# gigafoc.net
KiCad netlist of a schematic drawn in EAGLE
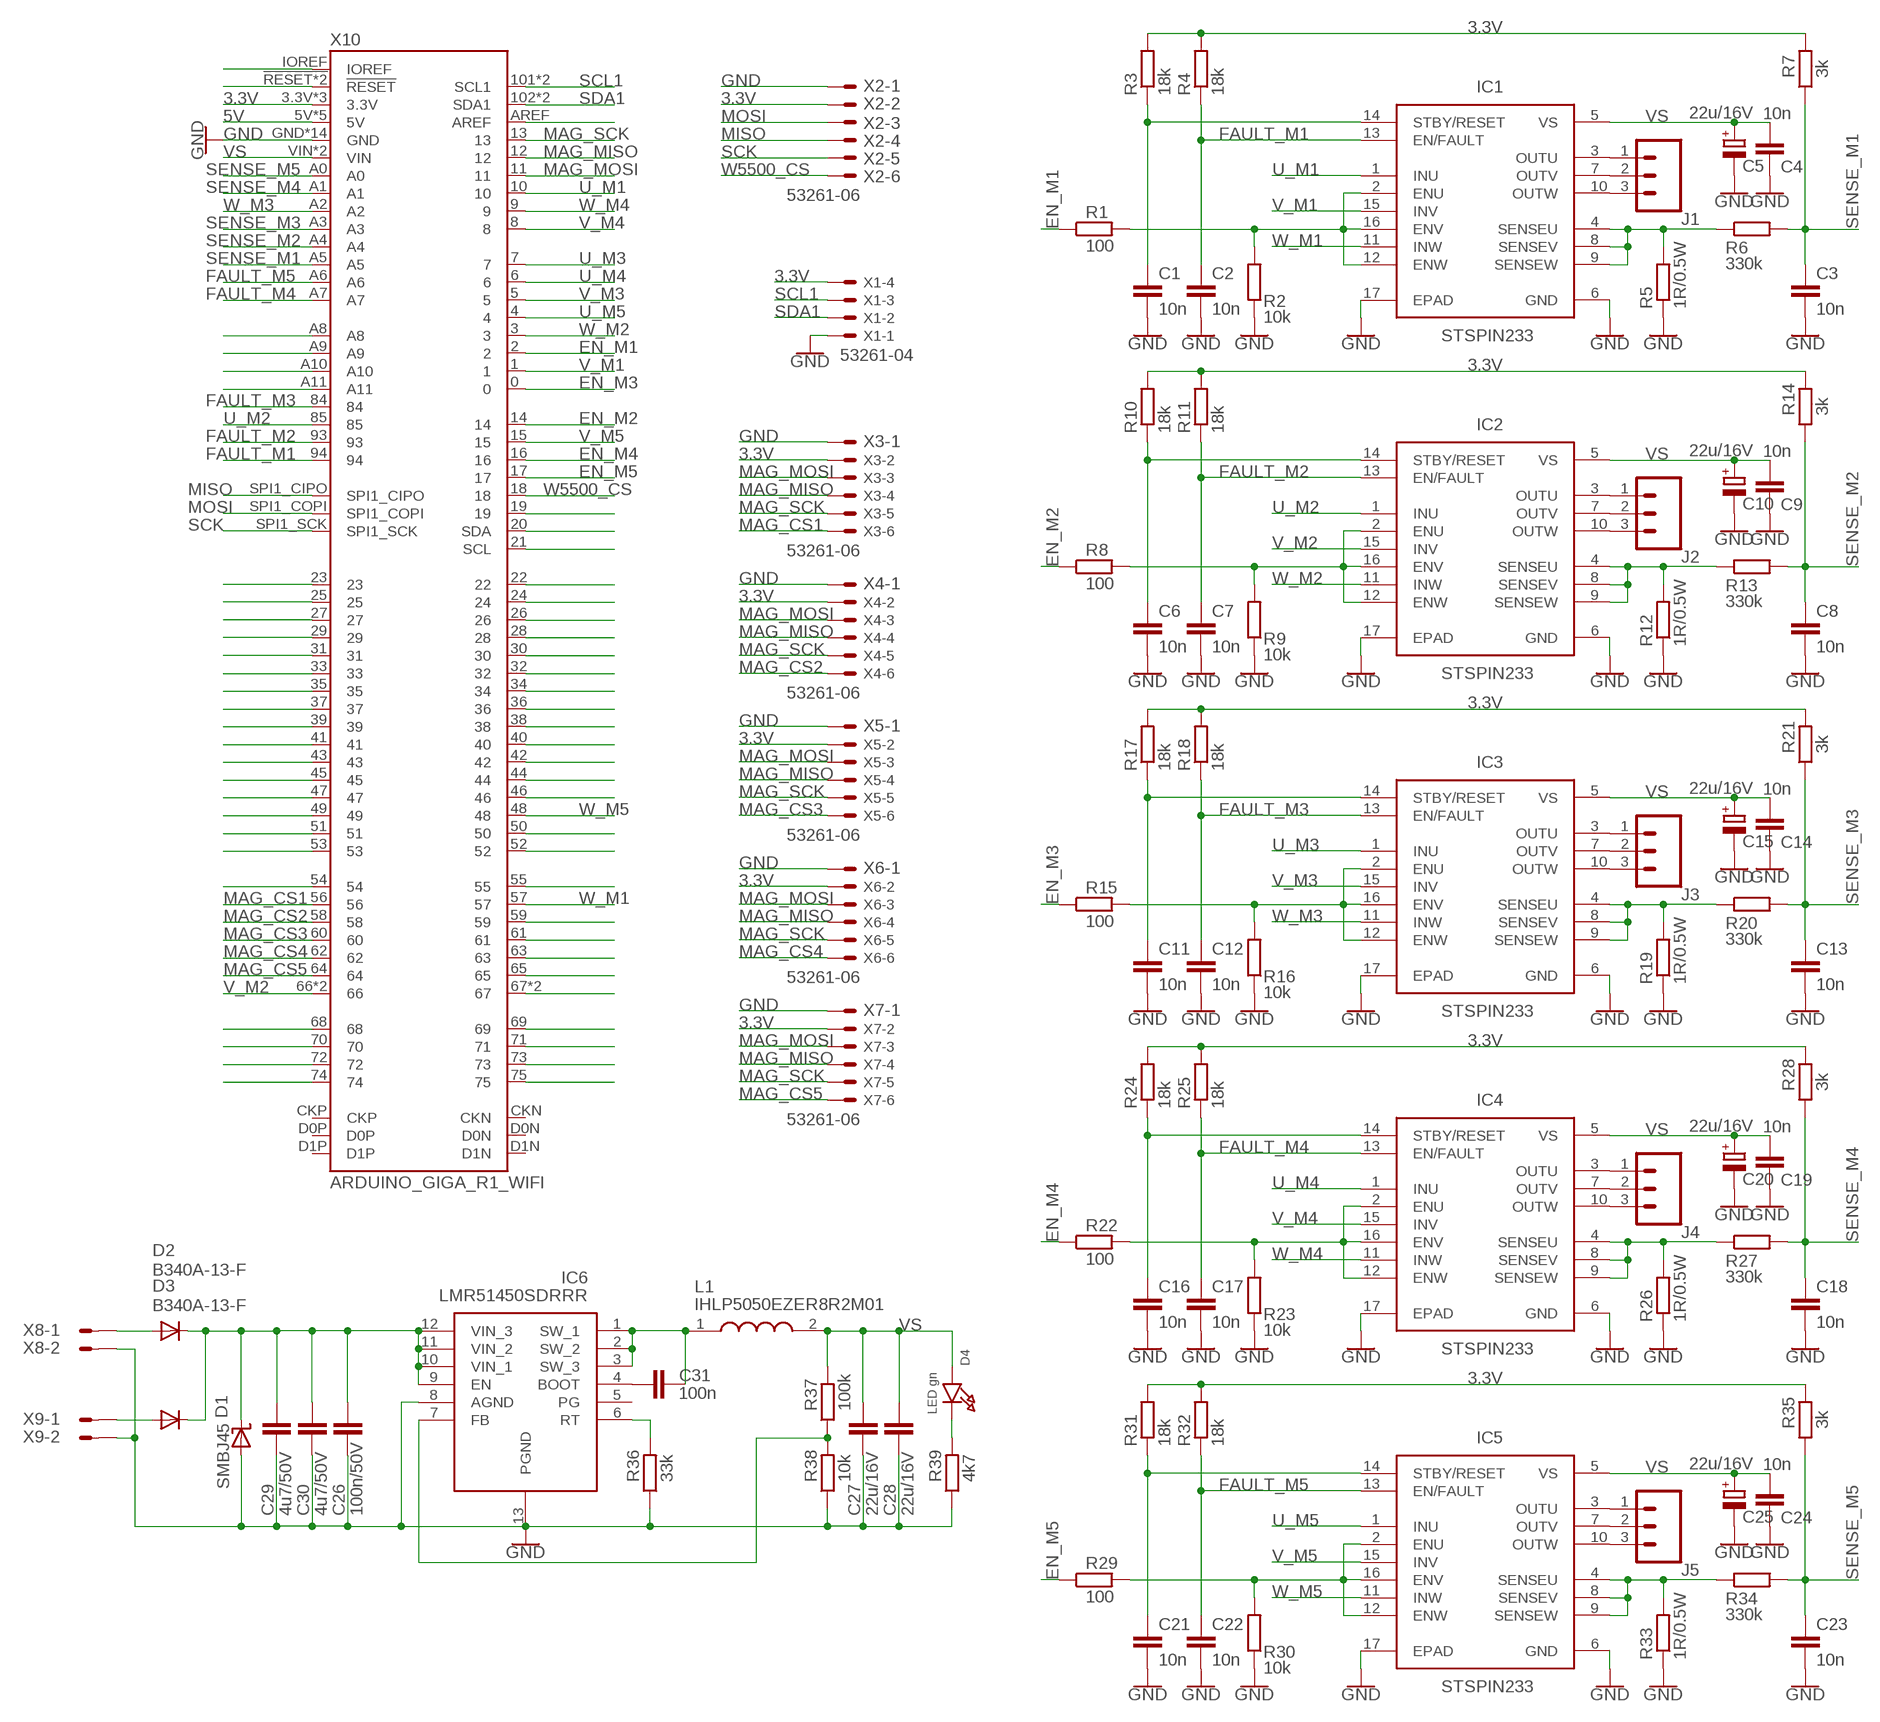
[diagram p0: schematic, sheet 1]

(export (version "E")
  (design (tool "Eeschema 10.0.6"))
  (components
    (comp (ref "C1")
      (value "10n")
      (footprint "eagle-import:C0603")
      (libsource (lib "eagle-import") (part "C-EUC0603"))
    )
    (comp (ref "C2")
      (value "10n")
      (footprint "eagle-import:C0603")
      (libsource (lib "eagle-import") (part "C-EUC0603"))
    )
    (comp (ref "C3")
      (value "10n")
      (footprint "eagle-import:C0603")
      (libsource (lib "eagle-import") (part "C-EUC0603"))
    )
    (comp (ref "C4")
      (value "10n")
      (footprint "eagle-import:C0603")
      (libsource (lib "eagle-import") (part "C-EUC0603"))
    )
    (comp (ref "C5")
      (value "22u/16V")
      (footprint "eagle-import:SMC_B")
      (libsource (lib "eagle-import") (part "CPOL-EUSMCB"))
    )
    (comp (ref "C6")
      (value "10n")
      (footprint "eagle-import:C0603")
      (libsource (lib "eagle-import") (part "C-EUC0603"))
    )
    (comp (ref "C7")
      (value "10n")
      (footprint "eagle-import:C0603")
      (libsource (lib "eagle-import") (part "C-EUC0603"))
    )
    (comp (ref "C8")
      (value "10n")
      (footprint "eagle-import:C0603")
      (libsource (lib "eagle-import") (part "C-EUC0603"))
    )
    (comp (ref "C9")
      (value "10n")
      (footprint "eagle-import:C0603")
      (libsource (lib "eagle-import") (part "C-EUC0603"))
    )
    (comp (ref "C10")
      (value "22u/16V")
      (footprint "eagle-import:SMC_B")
      (libsource (lib "eagle-import") (part "CPOL-EUSMCB"))
    )
    (comp (ref "C11")
      (value "10n")
      (footprint "eagle-import:C0603")
      (libsource (lib "eagle-import") (part "C-EUC0603"))
    )
    (comp (ref "C12")
      (value "10n")
      (footprint "eagle-import:C0603")
      (libsource (lib "eagle-import") (part "C-EUC0603"))
    )
    (comp (ref "C13")
      (value "10n")
      (footprint "eagle-import:C0603")
      (libsource (lib "eagle-import") (part "C-EUC0603"))
    )
    (comp (ref "C14")
      (value "10n")
      (footprint "eagle-import:C0603")
      (libsource (lib "eagle-import") (part "C-EUC0603"))
    )
    (comp (ref "C15")
      (value "22u/16V")
      (footprint "eagle-import:SMC_B")
      (libsource (lib "eagle-import") (part "CPOL-EUSMCB"))
    )
    (comp (ref "C16")
      (value "10n")
      (footprint "eagle-import:C0603")
      (libsource (lib "eagle-import") (part "C-EUC0603"))
    )
    (comp (ref "C17")
      (value "10n")
      (footprint "eagle-import:C0603")
      (libsource (lib "eagle-import") (part "C-EUC0603"))
    )
    (comp (ref "C18")
      (value "10n")
      (footprint "eagle-import:C0603")
      (libsource (lib "eagle-import") (part "C-EUC0603"))
    )
    (comp (ref "C19")
      (value "10n")
      (footprint "eagle-import:C0603")
      (libsource (lib "eagle-import") (part "C-EUC0603"))
    )
    (comp (ref "C20")
      (value "22u/16V")
      (footprint "eagle-import:SMC_B")
      (libsource (lib "eagle-import") (part "CPOL-EUSMCB"))
    )
    (comp (ref "C21")
      (value "10n")
      (footprint "eagle-import:C0603")
      (libsource (lib "eagle-import") (part "C-EUC0603"))
    )
    (comp (ref "C22")
      (value "10n")
      (footprint "eagle-import:C0603")
      (libsource (lib "eagle-import") (part "C-EUC0603"))
    )
    (comp (ref "C23")
      (value "10n")
      (footprint "eagle-import:C0603")
      (libsource (lib "eagle-import") (part "C-EUC0603"))
    )
    (comp (ref "C24")
      (value "10n")
      (footprint "eagle-import:C0603")
      (libsource (lib "eagle-import") (part "C-EUC0603"))
    )
    (comp (ref "C25")
      (value "22u/16V")
      (footprint "eagle-import:SMC_B")
      (libsource (lib "eagle-import") (part "CPOL-EUSMCB"))
    )
    (comp (ref "C26")
      (value "100n/50V")
      (footprint "eagle-import:C0805")
      (libsource (lib "eagle-import") (part "C-EUC0805"))
    )
    (comp (ref "C27")
      (value "22u/16V")
      (footprint "eagle-import:C1210")
      (libsource (lib "eagle-import") (part "C-EUC1210"))
    )
    (comp (ref "C28")
      (value "22u/16V")
      (footprint "eagle-import:C1210")
      (libsource (lib "eagle-import") (part "C-EUC1210"))
    )
    (comp (ref "C29")
      (value "4u7/50V")
      (footprint "eagle-import:C1210K")
      (libsource (lib "eagle-import") (part "C-EUC1210K"))
    )
    (comp (ref "C30")
      (value "4u7/50V")
      (footprint "eagle-import:C1210K")
      (libsource (lib "eagle-import") (part "C-EUC1210K"))
    )
    (comp (ref "C31")
      (value "100n")
      (footprint "eagle-import:C0603")
      (libsource (lib "eagle-import") (part "C-EUC0603"))
    )
    (comp (ref "D1")
      (value "SMBJ45")
      (footprint "eagle-import:SMBJ")
      (libsource (lib "eagle-import") (part "SUPPRESSOR-SMBJ"))
    )
    (comp (ref "D2")
      (value "B340A-13-F")
      (footprint "eagle-import:DO214AC")
      (libsource (lib "eagle-import") (part "DIODE-DO214AC"))
    )
    (comp (ref "D3")
      (value "B340A-13-F")
      (footprint "eagle-import:DO214AC")
      (libsource (lib "eagle-import") (part "DIODE-DO214AC"))
    )
    (comp (ref "D4")
      (value "LED gn")
      (footprint "eagle-import:CHIPLED_0603_NOOUTLINE")
      (libsource (lib "eagle-import") (part "LED0603_NOOUTLINE"))
    )
    (comp (ref "IC1")
      (value "STSPIN233")
      (footprint "eagle-import:QFN50P300X300X100-17N")
      (fields (field (name "MOUSER_PART_NUMBER") "511-STSPIN233"))
      (libsource (lib "eagle-import") (part "STSPIN233"))
    )
    (comp (ref "IC2")
      (value "STSPIN233")
      (footprint "eagle-import:QFN50P300X300X100-17N")
      (fields (field (name "MOUSER_PART_NUMBER") "511-STSPIN233"))
      (libsource (lib "eagle-import") (part "STSPIN233"))
    )
    (comp (ref "IC3")
      (value "STSPIN233")
      (footprint "eagle-import:QFN50P300X300X100-17N")
      (fields (field (name "MOUSER_PART_NUMBER") "511-STSPIN233"))
      (libsource (lib "eagle-import") (part "STSPIN233"))
    )
    (comp (ref "IC4")
      (value "STSPIN233")
      (footprint "eagle-import:QFN50P300X300X100-17N")
      (fields (field (name "MOUSER_PART_NUMBER") "511-STSPIN233"))
      (libsource (lib "eagle-import") (part "STSPIN233"))
    )
    (comp (ref "IC5")
      (value "STSPIN233")
      (footprint "eagle-import:QFN50P300X300X100-17N")
      (fields (field (name "MOUSER_PART_NUMBER") "511-STSPIN233"))
      (libsource (lib "eagle-import") (part "STSPIN233"))
    )
    (comp (ref "IC6")
      (value "LMR51450SDRRR")
      (footprint "eagle-import:SON50P300X300X80-13N")
      (fields (field (name "MOUSER_PART_NUMBER") "595-LMR51450SDRRR"))
      (libsource (lib "eagle-import") (part "LMR51450SDRRR"))
    )
    (comp (ref "J1")
      (value "CONN_03POLAR")
      (footprint "eagle-import:MOLEX-1X3")
      (libsource (lib "eagle-import") (part "CONN_03POLAR"))
    )
    (comp (ref "J2")
      (value "CONN_03POLAR")
      (footprint "eagle-import:MOLEX-1X3")
      (libsource (lib "eagle-import") (part "CONN_03POLAR"))
    )
    (comp (ref "J3")
      (value "CONN_03POLAR")
      (footprint "eagle-import:MOLEX-1X3")
      (libsource (lib "eagle-import") (part "CONN_03POLAR"))
    )
    (comp (ref "J4")
      (value "CONN_03POLAR")
      (footprint "eagle-import:MOLEX-1X3")
      (libsource (lib "eagle-import") (part "CONN_03POLAR"))
    )
    (comp (ref "J5")
      (value "CONN_03POLAR")
      (footprint "eagle-import:MOLEX-1X3")
      (libsource (lib "eagle-import") (part "CONN_03POLAR"))
    )
    (comp (ref "L1")
      (value "IHLP5050EZER8R2M01")
      (footprint "eagle-import:INDPM132129X500N")
      (fields (field (name "MOUSER_PART_NUMBER") "70-IHLP5050EZER8R2M1"))
      (libsource (lib "eagle-import") (part "IHLP5050EZER8R2M01"))
    )
    (comp (ref "R1")
      (value "100")
      (footprint "eagle-import:R0603")
      (libsource (lib "eagle-import") (part "R-EU_R0603"))
    )
    (comp (ref "R2")
      (value "10k")
      (footprint "eagle-import:R0603")
      (libsource (lib "eagle-import") (part "R-EU_R0603"))
    )
    (comp (ref "R3")
      (value "18k")
      (footprint "eagle-import:R0603")
      (libsource (lib "eagle-import") (part "R-EU_R0603"))
    )
    (comp (ref "R4")
      (value "18k")
      (footprint "eagle-import:R0603")
      (libsource (lib "eagle-import") (part "R-EU_R0603"))
    )
    (comp (ref "R5")
      (value "1R/0.5W")
      (footprint "eagle-import:R1206")
      (libsource (lib "eagle-import") (part "R-EU_R1206"))
    )
    (comp (ref "R6")
      (value "330k")
      (footprint "eagle-import:R0603")
      (libsource (lib "eagle-import") (part "R-EU_R0603"))
    )
    (comp (ref "R7")
      (value "3k")
      (footprint "eagle-import:R0603")
      (libsource (lib "eagle-import") (part "R-EU_R0603"))
    )
    (comp (ref "R8")
      (value "100")
      (footprint "eagle-import:R0603")
      (libsource (lib "eagle-import") (part "R-EU_R0603"))
    )
    (comp (ref "R9")
      (value "10k")
      (footprint "eagle-import:R0603")
      (libsource (lib "eagle-import") (part "R-EU_R0603"))
    )
    (comp (ref "R10")
      (value "18k")
      (footprint "eagle-import:R0603")
      (libsource (lib "eagle-import") (part "R-EU_R0603"))
    )
    (comp (ref "R11")
      (value "18k")
      (footprint "eagle-import:R0603")
      (libsource (lib "eagle-import") (part "R-EU_R0603"))
    )
    (comp (ref "R12")
      (value "1R/0.5W")
      (footprint "eagle-import:R1206")
      (libsource (lib "eagle-import") (part "R-EU_R1206"))
    )
    (comp (ref "R13")
      (value "330k")
      (footprint "eagle-import:R0603")
      (libsource (lib "eagle-import") (part "R-EU_R0603"))
    )
    (comp (ref "R14")
      (value "3k")
      (footprint "eagle-import:R0603")
      (libsource (lib "eagle-import") (part "R-EU_R0603"))
    )
    (comp (ref "R15")
      (value "100")
      (footprint "eagle-import:R0603")
      (libsource (lib "eagle-import") (part "R-EU_R0603"))
    )
    (comp (ref "R16")
      (value "10k")
      (footprint "eagle-import:R0603")
      (libsource (lib "eagle-import") (part "R-EU_R0603"))
    )
    (comp (ref "R17")
      (value "18k")
      (footprint "eagle-import:R0603")
      (libsource (lib "eagle-import") (part "R-EU_R0603"))
    )
    (comp (ref "R18")
      (value "18k")
      (footprint "eagle-import:R0603")
      (libsource (lib "eagle-import") (part "R-EU_R0603"))
    )
    (comp (ref "R19")
      (value "1R/0.5W")
      (footprint "eagle-import:R1206")
      (libsource (lib "eagle-import") (part "R-EU_R1206"))
    )
    (comp (ref "R20")
      (value "330k")
      (footprint "eagle-import:R0603")
      (libsource (lib "eagle-import") (part "R-EU_R0603"))
    )
    (comp (ref "R21")
      (value "3k")
      (footprint "eagle-import:R0603")
      (libsource (lib "eagle-import") (part "R-EU_R0603"))
    )
    (comp (ref "R22")
      (value "100")
      (footprint "eagle-import:R0603")
      (libsource (lib "eagle-import") (part "R-EU_R0603"))
    )
    (comp (ref "R23")
      (value "10k")
      (footprint "eagle-import:R0603")
      (libsource (lib "eagle-import") (part "R-EU_R0603"))
    )
    (comp (ref "R24")
      (value "18k")
      (footprint "eagle-import:R0603")
      (libsource (lib "eagle-import") (part "R-EU_R0603"))
    )
    (comp (ref "R25")
      (value "18k")
      (footprint "eagle-import:R0603")
      (libsource (lib "eagle-import") (part "R-EU_R0603"))
    )
    (comp (ref "R26")
      (value "1R/0.5W")
      (footprint "eagle-import:R1206")
      (libsource (lib "eagle-import") (part "R-EU_R1206"))
    )
    (comp (ref "R27")
      (value "330k")
      (footprint "eagle-import:R0603")
      (libsource (lib "eagle-import") (part "R-EU_R0603"))
    )
    (comp (ref "R28")
      (value "3k")
      (footprint "eagle-import:R0603")
      (libsource (lib "eagle-import") (part "R-EU_R0603"))
    )
    (comp (ref "R29")
      (value "100")
      (footprint "eagle-import:R0603")
      (libsource (lib "eagle-import") (part "R-EU_R0603"))
    )
    (comp (ref "R30")
      (value "10k")
      (footprint "eagle-import:R0603")
      (libsource (lib "eagle-import") (part "R-EU_R0603"))
    )
    (comp (ref "R31")
      (value "18k")
      (footprint "eagle-import:R0603")
      (libsource (lib "eagle-import") (part "R-EU_R0603"))
    )
    (comp (ref "R32")
      (value "18k")
      (footprint "eagle-import:R0603")
      (libsource (lib "eagle-import") (part "R-EU_R0603"))
    )
    (comp (ref "R33")
      (value "1R/0.5W")
      (footprint "eagle-import:R1206")
      (libsource (lib "eagle-import") (part "R-EU_R1206"))
    )
    (comp (ref "R34")
      (value "330k")
      (footprint "eagle-import:R0603")
      (libsource (lib "eagle-import") (part "R-EU_R0603"))
    )
    (comp (ref "R35")
      (value "3k")
      (footprint "eagle-import:R0603")
      (libsource (lib "eagle-import") (part "R-EU_R0603"))
    )
    (comp (ref "R36")
      (value "33k")
      (footprint "eagle-import:R0603")
      (libsource (lib "eagle-import") (part "R-EU_R0603"))
    )
    (comp (ref "R37")
      (value "100k")
      (footprint "eagle-import:R0603")
      (libsource (lib "eagle-import") (part "R-EU_R0603"))
    )
    (comp (ref "R38")
      (value "10k")
      (footprint "eagle-import:R0603")
      (libsource (lib "eagle-import") (part "R-EU_R0603"))
    )
    (comp (ref "R39")
      (value "4k7")
      (footprint "eagle-import:R0603")
      (libsource (lib "eagle-import") (part "R-EU_R0603"))
    )
    (comp (ref "X1")
      (value "53261-04")
      (footprint "eagle-import:53261-04")
      (fields (field (name "MF") "MOLEX"))
      (libsource (lib "eagle-import") (part "53?-04261"))
    )
    (comp (ref "X2")
      (value "53261-06")
      (footprint "eagle-import:53261-06")
      (fields (field (name "MF") "MOLEX"))
      (libsource (lib "eagle-import") (part "53?-06261"))
    )
    (comp (ref "X3")
      (value "53261-06")
      (footprint "eagle-import:53261-06")
      (fields (field (name "MF") "MOLEX"))
      (libsource (lib "eagle-import") (part "53?-06261"))
    )
    (comp (ref "X4")
      (value "53261-06")
      (footprint "eagle-import:53261-06")
      (fields (field (name "MF") "MOLEX"))
      (libsource (lib "eagle-import") (part "53?-06261"))
    )
    (comp (ref "X5")
      (value "53261-06")
      (footprint "eagle-import:53261-06")
      (fields (field (name "MF") "MOLEX"))
      (libsource (lib "eagle-import") (part "53?-06261"))
    )
    (comp (ref "X6")
      (value "53261-06")
      (footprint "eagle-import:53261-06")
      (fields (field (name "MF") "MOLEX"))
      (libsource (lib "eagle-import") (part "53?-06261"))
    )
    (comp (ref "X7")
      (value "53261-06")
      (footprint "eagle-import:53261-06")
      (fields (field (name "MF") "MOLEX"))
      (libsource (lib "eagle-import") (part "53?-06261"))
    )
    (comp (ref "X8")
      (value "S02P")
      (footprint "eagle-import:S02P")
      (libsource (lib "eagle-import") (part "S02P"))
    )
    (comp (ref "X9")
      (value "S02P")
      (footprint "eagle-import:S02P")
      (libsource (lib "eagle-import") (part "S02P"))
    )
    (comp (ref "X10")
      (value "ARDUINO_GIGA_R1_WIFI")
      (footprint "eagle-import:ARDUINO_GIGA_NO_SILK")
      (libsource (lib "eagle-import") (part "ARDUINO_GIGA_R1_WIFI"))
    )
  )
  (nets
    (net (code "1") (name "/3.3V") (class "Default")
      (node (ref "R10") (pin "2") (pinfunction "2_2") (pintype "passive"))
      (node (ref "R11") (pin "2") (pinfunction "2_2") (pintype "passive"))
      (node (ref "R14") (pin "2") (pinfunction "2_2") (pintype "passive"))
      (node (ref "R17") (pin "2") (pinfunction "2_2") (pintype "passive"))
      (node (ref "R18") (pin "2") (pinfunction "2_2") (pintype "passive"))
      (node (ref "R21") (pin "2") (pinfunction "2_2") (pintype "passive"))
      (node (ref "R24") (pin "2") (pinfunction "2_2") (pintype "passive"))
      (node (ref "R25") (pin "2") (pinfunction "2_2") (pintype "passive"))
      (node (ref "R28") (pin "2") (pinfunction "2_2") (pintype "passive"))
      (node (ref "R3") (pin "2") (pinfunction "2_2") (pintype "passive"))
      (node (ref "R31") (pin "2") (pinfunction "2_2") (pintype "passive"))
      (node (ref "R32") (pin "2") (pinfunction "2_2") (pintype "passive"))
      (node (ref "R35") (pin "2") (pinfunction "2_2") (pintype "passive"))
      (node (ref "R4") (pin "2") (pinfunction "2_2") (pintype "passive"))
      (node (ref "R7") (pin "2") (pinfunction "2_2") (pintype "passive"))
      (node (ref "X1") (pin "4") (pinfunction "S_4") (pintype "passive"))
      (node (ref "X10") (pin "3.3V") (pinfunction "3.3V_3.3V") (pintype "bidirectional"))
      (node (ref "X10") (pin "3.3V@1") (pinfunction "3.3V_3.3V@1") (pintype "bidirectional"))
      (node (ref "X10") (pin "3.3V@2") (pinfunction "3.3V_3.3V@2") (pintype "bidirectional"))
      (node (ref "X2") (pin "2") (pinfunction "S_2") (pintype "passive"))
      (node (ref "X3") (pin "2") (pinfunction "S_2") (pintype "passive"))
      (node (ref "X4") (pin "2") (pinfunction "S_2") (pintype "passive"))
      (node (ref "X5") (pin "2") (pinfunction "S_2") (pintype "passive"))
      (node (ref "X6") (pin "2") (pinfunction "S_2") (pintype "passive"))
      (node (ref "X7") (pin "2") (pinfunction "S_2") (pintype "passive"))
    )
    (net (code "2") (name "/5V") (class "Default")
      (node (ref "X10") (pin "5V") (pinfunction "5V_5V") (pintype "bidirectional"))
      (node (ref "X10") (pin "5V@1") (pinfunction "5V_5V@1") (pintype "bidirectional"))
      (node (ref "X10") (pin "5V@2") (pinfunction "5V_5V@2") (pintype "bidirectional"))
      (node (ref "X10") (pin "5V@3") (pinfunction "5V_5V@3") (pintype "bidirectional"))
      (node (ref "X10") (pin "5V@4") (pinfunction "5V_5V@4") (pintype "bidirectional"))
    )
    (net (code "3") (name "/EN_M1") (class "Default")
      (node (ref "R1") (pin "1") (pinfunction "1_1") (pintype "passive"))
      (node (ref "X10") (pin "2") (pinfunction "2_2") (pintype "bidirectional"))
    )
    (net (code "4") (name "/EN_M2") (class "Default")
      (node (ref "R8") (pin "1") (pinfunction "1_1") (pintype "passive"))
      (node (ref "X10") (pin "14") (pinfunction "14_14") (pintype "bidirectional"))
    )
    (net (code "5") (name "/EN_M3") (class "Default")
      (node (ref "R15") (pin "1") (pinfunction "1_1") (pintype "passive"))
      (node (ref "X10") (pin "0") (pinfunction "0_0") (pintype "bidirectional"))
    )
    (net (code "6") (name "/EN_M4") (class "Default")
      (node (ref "R22") (pin "1") (pinfunction "1_1") (pintype "passive"))
      (node (ref "X10") (pin "16") (pinfunction "16_16") (pintype "bidirectional"))
    )
    (net (code "7") (name "/EN_M5") (class "Default")
      (node (ref "R29") (pin "1") (pinfunction "1_1") (pintype "passive"))
      (node (ref "X10") (pin "17") (pinfunction "17_17") (pintype "bidirectional"))
    )
    (net (code "8") (name "/FAULT_M1") (class "Default")
      (node (ref "C2") (pin "2") (pinfunction "2_2") (pintype "passive"))
      (node (ref "IC1") (pin "13") (pinfunction "EN/FAULT_13") (pintype "bidirectional"))
      (node (ref "R4") (pin "1") (pinfunction "1_1") (pintype "passive"))
      (node (ref "X10") (pin "94") (pinfunction "94_94") (pintype "bidirectional"))
    )
    (net (code "9") (name "/FAULT_M2") (class "Default")
      (node (ref "C7") (pin "2") (pinfunction "2_2") (pintype "passive"))
      (node (ref "IC2") (pin "13") (pinfunction "EN/FAULT_13") (pintype "bidirectional"))
      (node (ref "R11") (pin "1") (pinfunction "1_1") (pintype "passive"))
      (node (ref "X10") (pin "93") (pinfunction "93_93") (pintype "bidirectional"))
    )
    (net (code "10") (name "/FAULT_M3") (class "Default")
      (node (ref "C12") (pin "2") (pinfunction "2_2") (pintype "passive"))
      (node (ref "IC3") (pin "13") (pinfunction "EN/FAULT_13") (pintype "bidirectional"))
      (node (ref "R18") (pin "1") (pinfunction "1_1") (pintype "passive"))
      (node (ref "X10") (pin "84") (pinfunction "84_84") (pintype "bidirectional"))
    )
    (net (code "11") (name "/FAULT_M4") (class "Default")
      (node (ref "C17") (pin "2") (pinfunction "2_2") (pintype "passive"))
      (node (ref "IC4") (pin "13") (pinfunction "EN/FAULT_13") (pintype "bidirectional"))
      (node (ref "R25") (pin "1") (pinfunction "1_1") (pintype "passive"))
      (node (ref "X10") (pin "A7") (pinfunction "A7_A7") (pintype "bidirectional"))
    )
    (net (code "12") (name "/FAULT_M5") (class "Default")
      (node (ref "C22") (pin "2") (pinfunction "2_2") (pintype "passive"))
      (node (ref "IC5") (pin "13") (pinfunction "EN/FAULT_13") (pintype "bidirectional"))
      (node (ref "R32") (pin "1") (pinfunction "1_1") (pintype "passive"))
      (node (ref "X10") (pin "A6") (pinfunction "A6_A6") (pintype "bidirectional"))
    )
    (net (code "13") (name "/MAG_CS1") (class "Default")
      (node (ref "X10") (pin "56") (pinfunction "56_56") (pintype "bidirectional"))
      (node (ref "X3") (pin "6") (pinfunction "S_6") (pintype "passive"))
    )
    (net (code "14") (name "/MAG_CS2") (class "Default")
      (node (ref "X10") (pin "58") (pinfunction "58_58") (pintype "bidirectional"))
      (node (ref "X4") (pin "6") (pinfunction "S_6") (pintype "passive"))
    )
    (net (code "15") (name "/MAG_CS3") (class "Default")
      (node (ref "X10") (pin "60") (pinfunction "60_60") (pintype "bidirectional"))
      (node (ref "X5") (pin "6") (pinfunction "S_6") (pintype "passive"))
    )
    (net (code "16") (name "/MAG_CS4") (class "Default")
      (node (ref "X10") (pin "62") (pinfunction "62_62") (pintype "bidirectional"))
      (node (ref "X6") (pin "6") (pinfunction "S_6") (pintype "passive"))
    )
    (net (code "17") (name "/MAG_CS5") (class "Default")
      (node (ref "X10") (pin "64") (pinfunction "64_64") (pintype "bidirectional"))
      (node (ref "X7") (pin "6") (pinfunction "S_6") (pintype "passive"))
    )
    (net (code "18") (name "/MAG_MISO") (class "Default")
      (node (ref "X10") (pin "12") (pinfunction "12_12") (pintype "bidirectional"))
      (node (ref "X3") (pin "4") (pinfunction "S_4") (pintype "passive"))
      (node (ref "X4") (pin "4") (pinfunction "S_4") (pintype "passive"))
      (node (ref "X5") (pin "4") (pinfunction "S_4") (pintype "passive"))
      (node (ref "X6") (pin "4") (pinfunction "S_4") (pintype "passive"))
      (node (ref "X7") (pin "4") (pinfunction "S_4") (pintype "passive"))
    )
    (net (code "19") (name "/MAG_MOSI") (class "Default")
      (node (ref "X10") (pin "11") (pinfunction "11_11") (pintype "bidirectional"))
      (node (ref "X3") (pin "3") (pinfunction "S_3") (pintype "passive"))
      (node (ref "X4") (pin "3") (pinfunction "S_3") (pintype "passive"))
      (node (ref "X5") (pin "3") (pinfunction "S_3") (pintype "passive"))
      (node (ref "X6") (pin "3") (pinfunction "S_3") (pintype "passive"))
      (node (ref "X7") (pin "3") (pinfunction "S_3") (pintype "passive"))
    )
    (net (code "20") (name "/MAG_SCK") (class "Default")
      (node (ref "X10") (pin "13") (pinfunction "13_13") (pintype "bidirectional"))
      (node (ref "X3") (pin "5") (pinfunction "S_5") (pintype "passive"))
      (node (ref "X4") (pin "5") (pinfunction "S_5") (pintype "passive"))
      (node (ref "X5") (pin "5") (pinfunction "S_5") (pintype "passive"))
      (node (ref "X6") (pin "5") (pinfunction "S_5") (pintype "passive"))
      (node (ref "X7") (pin "5") (pinfunction "S_5") (pintype "passive"))
    )
    (net (code "21") (name "/MISO") (class "Default")
      (node (ref "X10") (pin "SPI1_CIPO") (pinfunction "SPI1_CIPO_SPI1_CIPO") (pintype "bidirectional"))
      (node (ref "X2") (pin "4") (pinfunction "S_4") (pintype "passive"))
    )
    (net (code "22") (name "/MOSI") (class "Default")
      (node (ref "X10") (pin "SPI1_COPI") (pinfunction "SPI1_COPI_SPI1_COPI") (pintype "bidirectional"))
      (node (ref "X2") (pin "3") (pinfunction "S_3") (pintype "passive"))
    )
    (net (code "23") (name "/SCK") (class "Default")
      (node (ref "X10") (pin "SPI1_SCK") (pinfunction "SPI1_SCK_SPI1_SCK") (pintype "bidirectional"))
      (node (ref "X2") (pin "5") (pinfunction "S_5") (pintype "passive"))
    )
    (net (code "24") (name "/SCL1") (class "Default")
      (node (ref "X1") (pin "3") (pinfunction "S_3") (pintype "passive"))
      (node (ref "X10") (pin "101") (pinfunction "SCL1_101") (pintype "bidirectional"))
      (node (ref "X10") (pin "101@1") (pinfunction "SCL1_101@1") (pintype "bidirectional"))
    )
    (net (code "25") (name "/SDA1") (class "Default")
      (node (ref "X1") (pin "2") (pinfunction "S_2") (pintype "passive"))
      (node (ref "X10") (pin "102") (pinfunction "SDA1_102") (pintype "bidirectional"))
      (node (ref "X10") (pin "102@1") (pinfunction "SDA1_102@1") (pintype "bidirectional"))
    )
    (net (code "26") (name "/SENSE_M1") (class "Default")
      (node (ref "C3") (pin "2") (pinfunction "2_2") (pintype "passive"))
      (node (ref "R6") (pin "2") (pinfunction "2_2") (pintype "passive"))
      (node (ref "R7") (pin "1") (pinfunction "1_1") (pintype "passive"))
      (node (ref "X10") (pin "A5") (pinfunction "A5_A5") (pintype "bidirectional"))
    )
    (net (code "27") (name "/SENSE_M2") (class "Default")
      (node (ref "C8") (pin "2") (pinfunction "2_2") (pintype "passive"))
      (node (ref "R13") (pin "2") (pinfunction "2_2") (pintype "passive"))
      (node (ref "R14") (pin "1") (pinfunction "1_1") (pintype "passive"))
      (node (ref "X10") (pin "A4") (pinfunction "A4_A4") (pintype "bidirectional"))
    )
    (net (code "28") (name "/SENSE_M3") (class "Default")
      (node (ref "C13") (pin "2") (pinfunction "2_2") (pintype "passive"))
      (node (ref "R20") (pin "2") (pinfunction "2_2") (pintype "passive"))
      (node (ref "R21") (pin "1") (pinfunction "1_1") (pintype "passive"))
      (node (ref "X10") (pin "A3") (pinfunction "A3_A3") (pintype "bidirectional"))
    )
    (net (code "29") (name "/SENSE_M4") (class "Default")
      (node (ref "C18") (pin "2") (pinfunction "2_2") (pintype "passive"))
      (node (ref "R27") (pin "2") (pinfunction "2_2") (pintype "passive"))
      (node (ref "R28") (pin "1") (pinfunction "1_1") (pintype "passive"))
      (node (ref "X10") (pin "A1") (pinfunction "A1_A1") (pintype "bidirectional"))
    )
    (net (code "30") (name "/SENSE_M5") (class "Default")
      (node (ref "C23") (pin "2") (pinfunction "2_2") (pintype "passive"))
      (node (ref "R34") (pin "2") (pinfunction "2_2") (pintype "passive"))
      (node (ref "R35") (pin "1") (pinfunction "1_1") (pintype "passive"))
      (node (ref "X10") (pin "A0") (pinfunction "A0_A0") (pintype "bidirectional"))
    )
    (net (code "31") (name "/U_M1") (class "Default")
      (node (ref "IC1") (pin "1") (pinfunction "INU_1") (pintype "bidirectional"))
      (node (ref "X10") (pin "10") (pinfunction "10_10") (pintype "bidirectional"))
    )
    (net (code "32") (name "/U_M2") (class "Default")
      (node (ref "IC2") (pin "1") (pinfunction "INU_1") (pintype "bidirectional"))
      (node (ref "X10") (pin "85") (pinfunction "85_85") (pintype "bidirectional"))
    )
    (net (code "33") (name "/U_M3") (class "Default")
      (node (ref "IC3") (pin "1") (pinfunction "INU_1") (pintype "bidirectional"))
      (node (ref "X10") (pin "7") (pinfunction "7_7") (pintype "bidirectional"))
    )
    (net (code "34") (name "/U_M4") (class "Default")
      (node (ref "IC4") (pin "1") (pinfunction "INU_1") (pintype "bidirectional"))
      (node (ref "X10") (pin "6") (pinfunction "6_6") (pintype "bidirectional"))
    )
    (net (code "35") (name "/U_M5") (class "Default")
      (node (ref "IC5") (pin "1") (pinfunction "INU_1") (pintype "bidirectional"))
      (node (ref "X10") (pin "4") (pinfunction "4_4") (pintype "bidirectional"))
    )
    (net (code "36") (name "/VS") (class "Default")
      (node (ref "C10") (pin "+") (pinfunction "+_+") (pintype "passive"))
      (node (ref "C14") (pin "2") (pinfunction "2_2") (pintype "passive"))
      (node (ref "C15") (pin "+") (pinfunction "+_+") (pintype "passive"))
      (node (ref "C19") (pin "2") (pinfunction "2_2") (pintype "passive"))
      (node (ref "C20") (pin "+") (pinfunction "+_+") (pintype "passive"))
      (node (ref "C24") (pin "2") (pinfunction "2_2") (pintype "passive"))
      (node (ref "C25") (pin "+") (pinfunction "+_+") (pintype "passive"))
      (node (ref "C27") (pin "1") (pinfunction "1_1") (pintype "passive"))
      (node (ref "C28") (pin "1") (pinfunction "1_1") (pintype "passive"))
      (node (ref "C4") (pin "2") (pinfunction "2_2") (pintype "passive"))
      (node (ref "C5") (pin "+") (pinfunction "+_+") (pintype "passive"))
      (node (ref "C9") (pin "2") (pinfunction "2_2") (pintype "passive"))
      (node (ref "D4") (pin "A") (pinfunction "A_A") (pintype "passive"))
      (node (ref "IC1") (pin "5") (pinfunction "VS_5") (pintype "bidirectional"))
      (node (ref "IC2") (pin "5") (pinfunction "VS_5") (pintype "bidirectional"))
      (node (ref "IC3") (pin "5") (pinfunction "VS_5") (pintype "bidirectional"))
      (node (ref "IC4") (pin "5") (pinfunction "VS_5") (pintype "bidirectional"))
      (node (ref "IC5") (pin "5") (pinfunction "VS_5") (pintype "bidirectional"))
      (node (ref "L1") (pin "2") (pinfunction "2_2") (pintype "bidirectional"))
      (node (ref "R37") (pin "2") (pinfunction "2_2") (pintype "passive"))
      (node (ref "X10") (pin "VIN") (pinfunction "VIN_VIN") (pintype "bidirectional"))
      (node (ref "X10") (pin "VIN@1") (pinfunction "VIN_VIN@1") (pintype "bidirectional"))
    )
    (net (code "37") (name "/V_M1") (class "Default")
      (node (ref "IC1") (pin "15") (pinfunction "INV_15") (pintype "bidirectional"))
      (node (ref "X10") (pin "1") (pinfunction "1_1") (pintype "bidirectional"))
    )
    (net (code "38") (name "/V_M2") (class "Default")
      (node (ref "IC2") (pin "15") (pinfunction "INV_15") (pintype "bidirectional"))
      (node (ref "X10") (pin "66") (pinfunction "66_66") (pintype "bidirectional"))
      (node (ref "X10") (pin "66@1") (pinfunction "66_66@1") (pintype "bidirectional"))
    )
    (net (code "39") (name "/V_M3") (class "Default")
      (node (ref "IC3") (pin "15") (pinfunction "INV_15") (pintype "bidirectional"))
      (node (ref "X10") (pin "5") (pinfunction "5_5") (pintype "bidirectional"))
    )
    (net (code "40") (name "/V_M4") (class "Default")
      (node (ref "IC4") (pin "15") (pinfunction "INV_15") (pintype "bidirectional"))
      (node (ref "X10") (pin "8") (pinfunction "8_8") (pintype "bidirectional"))
    )
    (net (code "41") (name "/V_M5") (class "Default")
      (node (ref "IC5") (pin "15") (pinfunction "INV_15") (pintype "bidirectional"))
      (node (ref "X10") (pin "15") (pinfunction "15_15") (pintype "bidirectional"))
    )
    (net (code "42") (name "/W5500_CS") (class "Default")
      (node (ref "X10") (pin "18") (pinfunction "18_18") (pintype "bidirectional"))
      (node (ref "X2") (pin "6") (pinfunction "S_6") (pintype "passive"))
    )
    (net (code "43") (name "/W_M1") (class "Default")
      (node (ref "IC1") (pin "11") (pinfunction "INW_11") (pintype "bidirectional"))
      (node (ref "X10") (pin "57") (pinfunction "57_57") (pintype "bidirectional"))
    )
    (net (code "44") (name "/W_M2") (class "Default")
      (node (ref "IC2") (pin "11") (pinfunction "INW_11") (pintype "bidirectional"))
      (node (ref "X10") (pin "3") (pinfunction "3_3") (pintype "bidirectional"))
    )
    (net (code "45") (name "/W_M3") (class "Default")
      (node (ref "IC3") (pin "11") (pinfunction "INW_11") (pintype "bidirectional"))
      (node (ref "X10") (pin "A2") (pinfunction "A2_A2") (pintype "bidirectional"))
    )
    (net (code "46") (name "/W_M4") (class "Default")
      (node (ref "IC4") (pin "11") (pinfunction "INW_11") (pintype "bidirectional"))
      (node (ref "X10") (pin "9") (pinfunction "9_9") (pintype "bidirectional"))
    )
    (net (code "47") (name "/W_M5") (class "Default")
      (node (ref "IC5") (pin "11") (pinfunction "INW_11") (pintype "bidirectional"))
      (node (ref "X10") (pin "48") (pinfunction "48_48") (pintype "bidirectional"))
    )
    (net (code "48") (name "GND") (class "Default")
      (node (ref "C1") (pin "1") (pinfunction "1_1") (pintype "passive"))
      (node (ref "C10") (pin "-") (pinfunction "-_-") (pintype "passive"))
      (node (ref "C11") (pin "1") (pinfunction "1_1") (pintype "passive"))
      (node (ref "C12") (pin "1") (pinfunction "1_1") (pintype "passive"))
      (node (ref "C13") (pin "1") (pinfunction "1_1") (pintype "passive"))
      (node (ref "C14") (pin "1") (pinfunction "1_1") (pintype "passive"))
      (node (ref "C15") (pin "-") (pinfunction "-_-") (pintype "passive"))
      (node (ref "C16") (pin "1") (pinfunction "1_1") (pintype "passive"))
      (node (ref "C17") (pin "1") (pinfunction "1_1") (pintype "passive"))
      (node (ref "C18") (pin "1") (pinfunction "1_1") (pintype "passive"))
      (node (ref "C19") (pin "1") (pinfunction "1_1") (pintype "passive"))
      (node (ref "C2") (pin "1") (pinfunction "1_1") (pintype "passive"))
      (node (ref "C20") (pin "-") (pinfunction "-_-") (pintype "passive"))
      (node (ref "C21") (pin "1") (pinfunction "1_1") (pintype "passive"))
      (node (ref "C22") (pin "1") (pinfunction "1_1") (pintype "passive"))
      (node (ref "C23") (pin "1") (pinfunction "1_1") (pintype "passive"))
      (node (ref "C24") (pin "1") (pinfunction "1_1") (pintype "passive"))
      (node (ref "C25") (pin "-") (pinfunction "-_-") (pintype "passive"))
      (node (ref "C26") (pin "2") (pinfunction "2_2") (pintype "passive"))
      (node (ref "C27") (pin "2") (pinfunction "2_2") (pintype "passive"))
      (node (ref "C28") (pin "2") (pinfunction "2_2") (pintype "passive"))
      (node (ref "C29") (pin "2") (pinfunction "2_2") (pintype "passive"))
      (node (ref "C3") (pin "1") (pinfunction "1_1") (pintype "passive"))
      (node (ref "C30") (pin "2") (pinfunction "2_2") (pintype "passive"))
      (node (ref "C4") (pin "1") (pinfunction "1_1") (pintype "passive"))
      (node (ref "C5") (pin "-") (pinfunction "-_-") (pintype "passive"))
      (node (ref "C6") (pin "1") (pinfunction "1_1") (pintype "passive"))
      (node (ref "C7") (pin "1") (pinfunction "1_1") (pintype "passive"))
      (node (ref "C8") (pin "1") (pinfunction "1_1") (pintype "passive"))
      (node (ref "C9") (pin "1") (pinfunction "1_1") (pintype "passive"))
      (node (ref "D1") (pin "A") (pinfunction "A_A") (pintype "passive"))
      (node (ref "IC1") (pin "17") (pinfunction "EPAD_17") (pintype "bidirectional"))
      (node (ref "IC1") (pin "6") (pinfunction "GND_6") (pintype "bidirectional"))
      (node (ref "IC2") (pin "17") (pinfunction "EPAD_17") (pintype "bidirectional"))
      (node (ref "IC2") (pin "6") (pinfunction "GND_6") (pintype "bidirectional"))
      (node (ref "IC3") (pin "17") (pinfunction "EPAD_17") (pintype "bidirectional"))
      (node (ref "IC3") (pin "6") (pinfunction "GND_6") (pintype "bidirectional"))
      (node (ref "IC4") (pin "17") (pinfunction "EPAD_17") (pintype "bidirectional"))
      (node (ref "IC4") (pin "6") (pinfunction "GND_6") (pintype "bidirectional"))
      (node (ref "IC5") (pin "17") (pinfunction "EPAD_17") (pintype "bidirectional"))
      (node (ref "IC5") (pin "6") (pinfunction "GND_6") (pintype "bidirectional"))
      (node (ref "IC6") (pin "13") (pinfunction "PGND_13") (pintype "bidirectional"))
      (node (ref "IC6") (pin "8") (pinfunction "AGND_8") (pintype "bidirectional"))
      (node (ref "R12") (pin "1") (pinfunction "1_1") (pintype "passive"))
      (node (ref "R16") (pin "1") (pinfunction "1_1") (pintype "passive"))
      (node (ref "R19") (pin "1") (pinfunction "1_1") (pintype "passive"))
      (node (ref "R2") (pin "1") (pinfunction "1_1") (pintype "passive"))
      (node (ref "R23") (pin "1") (pinfunction "1_1") (pintype "passive"))
      (node (ref "R26") (pin "1") (pinfunction "1_1") (pintype "passive"))
      (node (ref "R30") (pin "1") (pinfunction "1_1") (pintype "passive"))
      (node (ref "R33") (pin "1") (pinfunction "1_1") (pintype "passive"))
      (node (ref "R36") (pin "1") (pinfunction "1_1") (pintype "passive"))
      (node (ref "R38") (pin "1") (pinfunction "1_1") (pintype "passive"))
      (node (ref "R39") (pin "1") (pinfunction "1_1") (pintype "passive"))
      (node (ref "R5") (pin "1") (pinfunction "1_1") (pintype "passive"))
      (node (ref "R9") (pin "1") (pinfunction "1_1") (pintype "passive"))
      (node (ref "X1") (pin "1") (pinfunction "S_1") (pintype "passive"))
      (node (ref "X10") (pin "GND") (pinfunction "GND_GND") (pintype "bidirectional"))
      (node (ref "X10") (pin "GND@1") (pinfunction "GND_GND@1") (pintype "bidirectional"))
      (node (ref "X10") (pin "GND@10") (pinfunction "GND_GND@10") (pintype "bidirectional"))
      (node (ref "X10") (pin "GND@11") (pinfunction "GND_GND@11") (pintype "bidirectional"))
      (node (ref "X10") (pin "GND@12") (pinfunction "GND_GND@12") (pintype "bidirectional"))
      (node (ref "X10") (pin "GND@13") (pinfunction "GND_GND@13") (pintype "bidirectional"))
      (node (ref "X10") (pin "GND@2") (pinfunction "GND_GND@2") (pintype "bidirectional"))
      (node (ref "X10") (pin "GND@3") (pinfunction "GND_GND@3") (pintype "bidirectional"))
      (node (ref "X10") (pin "GND@4") (pinfunction "GND_GND@4") (pintype "bidirectional"))
      (node (ref "X10") (pin "GND@5") (pinfunction "GND_GND@5") (pintype "bidirectional"))
      (node (ref "X10") (pin "GND@6") (pinfunction "GND_GND@6") (pintype "bidirectional"))
      (node (ref "X10") (pin "GND@7") (pinfunction "GND_GND@7") (pintype "bidirectional"))
      (node (ref "X10") (pin "GND@8") (pinfunction "GND_GND@8") (pintype "bidirectional"))
      (node (ref "X10") (pin "GND@9") (pinfunction "GND_GND@9") (pintype "bidirectional"))
      (node (ref "X2") (pin "1") (pinfunction "S_1") (pintype "passive"))
      (node (ref "X3") (pin "1") (pinfunction "S_1") (pintype "passive"))
      (node (ref "X4") (pin "1") (pinfunction "S_1") (pintype "passive"))
      (node (ref "X5") (pin "1") (pinfunction "S_1") (pintype "passive"))
      (node (ref "X6") (pin "1") (pinfunction "S_1") (pintype "passive"))
      (node (ref "X7") (pin "1") (pinfunction "S_1") (pintype "passive"))
      (node (ref "X8") (pin "2") (pinfunction "S_2") (pintype "passive"))
      (node (ref "X9") (pin "2") (pinfunction "S_2") (pintype "passive"))
    )
    (net (code "49") (name "Net-(D4-PadC)") (class "Default")
      (node (ref "D4") (pin "C") (pinfunction "C_C") (pintype "passive"))
      (node (ref "R39") (pin "2") (pinfunction "2_2") (pintype "passive"))
    )
    (net (code "50") (name "Net-(IC1-ENU)") (class "Default")
      (node (ref "IC1") (pin "12") (pinfunction "ENW_12") (pintype "bidirectional"))
      (node (ref "IC1") (pin "16") (pinfunction "ENV_16") (pintype "bidirectional"))
      (node (ref "IC1") (pin "2") (pinfunction "ENU_2") (pintype "bidirectional"))
      (node (ref "R1") (pin "2") (pinfunction "2_2") (pintype "passive"))
      (node (ref "R2") (pin "2") (pinfunction "2_2") (pintype "passive"))
    )
    (net (code "51") (name "Net-(IC1-OUTU)") (class "Default")
      (node (ref "IC1") (pin "3") (pinfunction "OUTU_3") (pintype "bidirectional"))
      (node (ref "J1") (pin "1") (pinfunction "1_1") (pintype "passive"))
    )
    (net (code "52") (name "Net-(IC1-OUTV)") (class "Default")
      (node (ref "IC1") (pin "7") (pinfunction "OUTV_7") (pintype "bidirectional"))
      (node (ref "J1") (pin "2") (pinfunction "2_2") (pintype "passive"))
    )
    (net (code "53") (name "Net-(IC1-OUTW)") (class "Default")
      (node (ref "IC1") (pin "10") (pinfunction "OUTW_10") (pintype "bidirectional"))
      (node (ref "J1") (pin "3") (pinfunction "3_3") (pintype "passive"))
    )
    (net (code "54") (name "Net-(IC1-SENSEU)") (class "Default")
      (node (ref "IC1") (pin "4") (pinfunction "SENSEU_4") (pintype "bidirectional"))
      (node (ref "IC1") (pin "8") (pinfunction "SENSEV_8") (pintype "bidirectional"))
      (node (ref "IC1") (pin "9") (pinfunction "SENSEW_9") (pintype "bidirectional"))
      (node (ref "R5") (pin "2") (pinfunction "2_2") (pintype "passive"))
      (node (ref "R6") (pin "1") (pinfunction "1_1") (pintype "passive"))
    )
    (net (code "55") (name "Net-(IC1-STBY{slash}RESET)") (class "Default")
      (node (ref "C1") (pin "2") (pinfunction "2_2") (pintype "passive"))
      (node (ref "IC1") (pin "14") (pinfunction "STBY/RESET_14") (pintype "bidirectional"))
      (node (ref "R3") (pin "1") (pinfunction "1_1") (pintype "passive"))
    )
    (net (code "56") (name "Net-(IC2-ENU)") (class "Default")
      (node (ref "IC2") (pin "12") (pinfunction "ENW_12") (pintype "bidirectional"))
      (node (ref "IC2") (pin "16") (pinfunction "ENV_16") (pintype "bidirectional"))
      (node (ref "IC2") (pin "2") (pinfunction "ENU_2") (pintype "bidirectional"))
      (node (ref "R8") (pin "2") (pinfunction "2_2") (pintype "passive"))
      (node (ref "R9") (pin "2") (pinfunction "2_2") (pintype "passive"))
    )
    (net (code "57") (name "Net-(IC2-OUTU)") (class "Default")
      (node (ref "IC2") (pin "3") (pinfunction "OUTU_3") (pintype "bidirectional"))
      (node (ref "J2") (pin "1") (pinfunction "1_1") (pintype "passive"))
    )
    (net (code "58") (name "Net-(IC2-OUTV)") (class "Default")
      (node (ref "IC2") (pin "7") (pinfunction "OUTV_7") (pintype "bidirectional"))
      (node (ref "J2") (pin "2") (pinfunction "2_2") (pintype "passive"))
    )
    (net (code "59") (name "Net-(IC2-OUTW)") (class "Default")
      (node (ref "IC2") (pin "10") (pinfunction "OUTW_10") (pintype "bidirectional"))
      (node (ref "J2") (pin "3") (pinfunction "3_3") (pintype "passive"))
    )
    (net (code "60") (name "Net-(IC2-SENSEU)") (class "Default")
      (node (ref "IC2") (pin "4") (pinfunction "SENSEU_4") (pintype "bidirectional"))
      (node (ref "IC2") (pin "8") (pinfunction "SENSEV_8") (pintype "bidirectional"))
      (node (ref "IC2") (pin "9") (pinfunction "SENSEW_9") (pintype "bidirectional"))
      (node (ref "R12") (pin "2") (pinfunction "2_2") (pintype "passive"))
      (node (ref "R13") (pin "1") (pinfunction "1_1") (pintype "passive"))
    )
    (net (code "61") (name "Net-(IC2-STBY{slash}RESET)") (class "Default")
      (node (ref "C6") (pin "2") (pinfunction "2_2") (pintype "passive"))
      (node (ref "IC2") (pin "14") (pinfunction "STBY/RESET_14") (pintype "bidirectional"))
      (node (ref "R10") (pin "1") (pinfunction "1_1") (pintype "passive"))
    )
    (net (code "62") (name "Net-(IC3-ENU)") (class "Default")
      (node (ref "IC3") (pin "12") (pinfunction "ENW_12") (pintype "bidirectional"))
      (node (ref "IC3") (pin "16") (pinfunction "ENV_16") (pintype "bidirectional"))
      (node (ref "IC3") (pin "2") (pinfunction "ENU_2") (pintype "bidirectional"))
      (node (ref "R15") (pin "2") (pinfunction "2_2") (pintype "passive"))
      (node (ref "R16") (pin "2") (pinfunction "2_2") (pintype "passive"))
    )
    (net (code "63") (name "Net-(IC3-OUTU)") (class "Default")
      (node (ref "IC3") (pin "3") (pinfunction "OUTU_3") (pintype "bidirectional"))
      (node (ref "J3") (pin "1") (pinfunction "1_1") (pintype "passive"))
    )
    (net (code "64") (name "Net-(IC3-OUTV)") (class "Default")
      (node (ref "IC3") (pin "7") (pinfunction "OUTV_7") (pintype "bidirectional"))
      (node (ref "J3") (pin "2") (pinfunction "2_2") (pintype "passive"))
    )
    (net (code "65") (name "Net-(IC3-OUTW)") (class "Default")
      (node (ref "IC3") (pin "10") (pinfunction "OUTW_10") (pintype "bidirectional"))
      (node (ref "J3") (pin "3") (pinfunction "3_3") (pintype "passive"))
    )
    (net (code "66") (name "Net-(IC3-SENSEU)") (class "Default")
      (node (ref "IC3") (pin "4") (pinfunction "SENSEU_4") (pintype "bidirectional"))
      (node (ref "IC3") (pin "8") (pinfunction "SENSEV_8") (pintype "bidirectional"))
      (node (ref "IC3") (pin "9") (pinfunction "SENSEW_9") (pintype "bidirectional"))
      (node (ref "R19") (pin "2") (pinfunction "2_2") (pintype "passive"))
      (node (ref "R20") (pin "1") (pinfunction "1_1") (pintype "passive"))
    )
    (net (code "67") (name "Net-(IC3-STBY{slash}RESET)") (class "Default")
      (node (ref "C11") (pin "2") (pinfunction "2_2") (pintype "passive"))
      (node (ref "IC3") (pin "14") (pinfunction "STBY/RESET_14") (pintype "bidirectional"))
      (node (ref "R17") (pin "1") (pinfunction "1_1") (pintype "passive"))
    )
    (net (code "68") (name "Net-(IC4-ENU)") (class "Default")
      (node (ref "IC4") (pin "12") (pinfunction "ENW_12") (pintype "bidirectional"))
      (node (ref "IC4") (pin "16") (pinfunction "ENV_16") (pintype "bidirectional"))
      (node (ref "IC4") (pin "2") (pinfunction "ENU_2") (pintype "bidirectional"))
      (node (ref "R22") (pin "2") (pinfunction "2_2") (pintype "passive"))
      (node (ref "R23") (pin "2") (pinfunction "2_2") (pintype "passive"))
    )
    (net (code "69") (name "Net-(IC4-OUTU)") (class "Default")
      (node (ref "IC4") (pin "3") (pinfunction "OUTU_3") (pintype "bidirectional"))
      (node (ref "J4") (pin "1") (pinfunction "1_1") (pintype "passive"))
    )
    (net (code "70") (name "Net-(IC4-OUTV)") (class "Default")
      (node (ref "IC4") (pin "7") (pinfunction "OUTV_7") (pintype "bidirectional"))
      (node (ref "J4") (pin "2") (pinfunction "2_2") (pintype "passive"))
    )
    (net (code "71") (name "Net-(IC4-OUTW)") (class "Default")
      (node (ref "IC4") (pin "10") (pinfunction "OUTW_10") (pintype "bidirectional"))
      (node (ref "J4") (pin "3") (pinfunction "3_3") (pintype "passive"))
    )
    (net (code "72") (name "Net-(IC4-SENSEU)") (class "Default")
      (node (ref "IC4") (pin "4") (pinfunction "SENSEU_4") (pintype "bidirectional"))
      (node (ref "IC4") (pin "8") (pinfunction "SENSEV_8") (pintype "bidirectional"))
      (node (ref "IC4") (pin "9") (pinfunction "SENSEW_9") (pintype "bidirectional"))
      (node (ref "R26") (pin "2") (pinfunction "2_2") (pintype "passive"))
      (node (ref "R27") (pin "1") (pinfunction "1_1") (pintype "passive"))
    )
    (net (code "73") (name "Net-(IC4-STBY{slash}RESET)") (class "Default")
      (node (ref "C16") (pin "2") (pinfunction "2_2") (pintype "passive"))
      (node (ref "IC4") (pin "14") (pinfunction "STBY/RESET_14") (pintype "bidirectional"))
      (node (ref "R24") (pin "1") (pinfunction "1_1") (pintype "passive"))
    )
    (net (code "74") (name "Net-(IC5-ENU)") (class "Default")
      (node (ref "IC5") (pin "12") (pinfunction "ENW_12") (pintype "bidirectional"))
      (node (ref "IC5") (pin "16") (pinfunction "ENV_16") (pintype "bidirectional"))
      (node (ref "IC5") (pin "2") (pinfunction "ENU_2") (pintype "bidirectional"))
      (node (ref "R29") (pin "2") (pinfunction "2_2") (pintype "passive"))
      (node (ref "R30") (pin "2") (pinfunction "2_2") (pintype "passive"))
    )
    (net (code "75") (name "Net-(IC5-OUTU)") (class "Default")
      (node (ref "IC5") (pin "3") (pinfunction "OUTU_3") (pintype "bidirectional"))
      (node (ref "J5") (pin "1") (pinfunction "1_1") (pintype "passive"))
    )
    (net (code "76") (name "Net-(IC5-OUTV)") (class "Default")
      (node (ref "IC5") (pin "7") (pinfunction "OUTV_7") (pintype "bidirectional"))
      (node (ref "J5") (pin "2") (pinfunction "2_2") (pintype "passive"))
    )
    (net (code "77") (name "Net-(IC5-OUTW)") (class "Default")
      (node (ref "IC5") (pin "10") (pinfunction "OUTW_10") (pintype "bidirectional"))
      (node (ref "J5") (pin "3") (pinfunction "3_3") (pintype "passive"))
    )
    (net (code "78") (name "Net-(IC5-SENSEU)") (class "Default")
      (node (ref "IC5") (pin "4") (pinfunction "SENSEU_4") (pintype "bidirectional"))
      (node (ref "IC5") (pin "8") (pinfunction "SENSEV_8") (pintype "bidirectional"))
      (node (ref "IC5") (pin "9") (pinfunction "SENSEW_9") (pintype "bidirectional"))
      (node (ref "R33") (pin "2") (pinfunction "2_2") (pintype "passive"))
      (node (ref "R34") (pin "1") (pinfunction "1_1") (pintype "passive"))
    )
    (net (code "79") (name "Net-(IC5-STBY{slash}RESET)") (class "Default")
      (node (ref "C21") (pin "2") (pinfunction "2_2") (pintype "passive"))
      (node (ref "IC5") (pin "14") (pinfunction "STBY/RESET_14") (pintype "bidirectional"))
      (node (ref "R31") (pin "1") (pinfunction "1_1") (pintype "passive"))
    )
    (net (code "80") (name "Net-(IC6-BOOT)") (class "Default")
      (node (ref "C31") (pin "1") (pinfunction "1_1") (pintype "passive"))
      (node (ref "IC6") (pin "4") (pinfunction "BOOT_4") (pintype "bidirectional"))
    )
    (net (code "81") (name "Net-(IC6-EN)") (class "Default")
      (node (ref "C26") (pin "1") (pinfunction "1_1") (pintype "passive"))
      (node (ref "C29") (pin "1") (pinfunction "1_1") (pintype "passive"))
      (node (ref "C30") (pin "1") (pinfunction "1_1") (pintype "passive"))
      (node (ref "D1") (pin "C") (pinfunction "C_C") (pintype "passive"))
      (node (ref "D2") (pin "C") (pinfunction "C_C") (pintype "passive"))
      (node (ref "D3") (pin "C") (pinfunction "C_C") (pintype "passive"))
      (node (ref "IC6") (pin "10") (pinfunction "VIN_1_10") (pintype "bidirectional"))
      (node (ref "IC6") (pin "11") (pinfunction "VIN_2_11") (pintype "bidirectional"))
      (node (ref "IC6") (pin "12") (pinfunction "VIN_3_12") (pintype "bidirectional"))
      (node (ref "IC6") (pin "9") (pinfunction "EN_9") (pintype "bidirectional"))
    )
    (net (code "82") (name "Net-(IC6-FB)") (class "Default")
      (node (ref "IC6") (pin "7") (pinfunction "FB_7") (pintype "bidirectional"))
      (node (ref "R37") (pin "1") (pinfunction "1_1") (pintype "passive"))
      (node (ref "R38") (pin "2") (pinfunction "2_2") (pintype "passive"))
    )
    (net (code "83") (name "Net-(IC6-RT)") (class "Default")
      (node (ref "IC6") (pin "6") (pinfunction "RT_6") (pintype "bidirectional"))
      (node (ref "R36") (pin "2") (pinfunction "2_2") (pintype "passive"))
    )
    (net (code "84") (name "Net-(IC6-SW_1)") (class "Default")
      (node (ref "C31") (pin "2") (pinfunction "2_2") (pintype "passive"))
      (node (ref "IC6") (pin "1") (pinfunction "SW_1_1") (pintype "bidirectional"))
      (node (ref "IC6") (pin "2") (pinfunction "SW_2_2") (pintype "bidirectional"))
      (node (ref "IC6") (pin "3") (pinfunction "SW_3_3") (pintype "bidirectional"))
      (node (ref "L1") (pin "1") (pinfunction "1_1") (pintype "bidirectional"))
    )
    (net (code "85") (name "Net-(X8A-S)") (class "Default")
      (node (ref "D2") (pin "A") (pinfunction "A_A") (pintype "passive"))
      (node (ref "X8") (pin "1") (pinfunction "S_1") (pintype "passive"))
    )
    (net (code "86") (name "Net-(X9A-S)") (class "Default")
      (node (ref "D3") (pin "A") (pinfunction "A_A") (pintype "passive"))
      (node (ref "X9") (pin "1") (pinfunction "S_1") (pintype "passive"))
    )
    (net (code "87") (name "Net-(X10-67-Pad67@1)") (class "Default")
      (node (ref "X10") (pin "67") (pinfunction "67_67") (pintype "bidirectional"))
      (node (ref "X10") (pin "67@1") (pinfunction "67_67@1") (pintype "bidirectional"))
    )
    (net (code "88") (name "Net-(X10-~{RESET}-Pad!RESET)") (class "Default")
      (node (ref "X10") (pin "!RESET") (pinfunction "~{RESET}_!RESET") (pintype "bidirectional"))
      (node (ref "X10") (pin "RESET") (pinfunction "~{RESET}_RESET") (pintype "bidirectional"))
    )
    (net (code "89") (name "unconnected-(IC6-PG-Pad5)") (class "Default")
      (node (ref "IC6") (pin "5") (pinfunction "PG_5") (pintype "bidirectional"))
    )
    (net (code "90") (name "unconnected-(X10-Pad19)") (class "Default")
      (node (ref "X10") (pin "19") (pinfunction "19_19") (pintype "bidirectional"))
    )
    (net (code "91") (name "unconnected-(X10-Pad22)") (class "Default")
      (node (ref "X10") (pin "22") (pinfunction "22_22") (pintype "bidirectional"))
    )
    (net (code "92") (name "unconnected-(X10-Pad23)") (class "Default")
      (node (ref "X10") (pin "23") (pinfunction "23_23") (pintype "bidirectional"))
    )
    (net (code "93") (name "unconnected-(X10-Pad24)") (class "Default")
      (node (ref "X10") (pin "24") (pinfunction "24_24") (pintype "bidirectional"))
    )
    (net (code "94") (name "unconnected-(X10-Pad25)") (class "Default")
      (node (ref "X10") (pin "25") (pinfunction "25_25") (pintype "bidirectional"))
    )
    (net (code "95") (name "unconnected-(X10-Pad26)") (class "Default")
      (node (ref "X10") (pin "26") (pinfunction "26_26") (pintype "bidirectional"))
    )
    (net (code "96") (name "unconnected-(X10-Pad27)") (class "Default")
      (node (ref "X10") (pin "27") (pinfunction "27_27") (pintype "bidirectional"))
    )
    (net (code "97") (name "unconnected-(X10-Pad28)") (class "Default")
      (node (ref "X10") (pin "28") (pinfunction "28_28") (pintype "bidirectional"))
    )
    (net (code "98") (name "unconnected-(X10-Pad29)") (class "Default")
      (node (ref "X10") (pin "29") (pinfunction "29_29") (pintype "bidirectional"))
    )
    (net (code "99") (name "unconnected-(X10-Pad30)") (class "Default")
      (node (ref "X10") (pin "30") (pinfunction "30_30") (pintype "bidirectional"))
    )
    (net (code "100") (name "unconnected-(X10-Pad31)") (class "Default")
      (node (ref "X10") (pin "31") (pinfunction "31_31") (pintype "bidirectional"))
    )
    (net (code "101") (name "unconnected-(X10-Pad32)") (class "Default")
      (node (ref "X10") (pin "32") (pinfunction "32_32") (pintype "bidirectional"))
    )
    (net (code "102") (name "unconnected-(X10-Pad33)") (class "Default")
      (node (ref "X10") (pin "33") (pinfunction "33_33") (pintype "bidirectional"))
    )
    (net (code "103") (name "unconnected-(X10-Pad34)") (class "Default")
      (node (ref "X10") (pin "34") (pinfunction "34_34") (pintype "bidirectional"))
    )
    (net (code "104") (name "unconnected-(X10-Pad35)") (class "Default")
      (node (ref "X10") (pin "35") (pinfunction "35_35") (pintype "bidirectional"))
    )
    (net (code "105") (name "unconnected-(X10-Pad36)") (class "Default")
      (node (ref "X10") (pin "36") (pinfunction "36_36") (pintype "bidirectional"))
    )
    (net (code "106") (name "unconnected-(X10-Pad37)") (class "Default")
      (node (ref "X10") (pin "37") (pinfunction "37_37") (pintype "bidirectional"))
    )
    (net (code "107") (name "unconnected-(X10-Pad38)") (class "Default")
      (node (ref "X10") (pin "38") (pinfunction "38_38") (pintype "bidirectional"))
    )
    (net (code "108") (name "unconnected-(X10-Pad39)") (class "Default")
      (node (ref "X10") (pin "39") (pinfunction "39_39") (pintype "bidirectional"))
    )
    (net (code "109") (name "unconnected-(X10-Pad40)") (class "Default")
      (node (ref "X10") (pin "40") (pinfunction "40_40") (pintype "bidirectional"))
    )
    (net (code "110") (name "unconnected-(X10-Pad41)") (class "Default")
      (node (ref "X10") (pin "41") (pinfunction "41_41") (pintype "bidirectional"))
    )
    (net (code "111") (name "unconnected-(X10-Pad42)") (class "Default")
      (node (ref "X10") (pin "42") (pinfunction "42_42") (pintype "bidirectional"))
    )
    (net (code "112") (name "unconnected-(X10-Pad43)") (class "Default")
      (node (ref "X10") (pin "43") (pinfunction "43_43") (pintype "bidirectional"))
    )
    (net (code "113") (name "unconnected-(X10-Pad44)") (class "Default")
      (node (ref "X10") (pin "44") (pinfunction "44_44") (pintype "bidirectional"))
    )
    (net (code "114") (name "unconnected-(X10-Pad45)") (class "Default")
      (node (ref "X10") (pin "45") (pinfunction "45_45") (pintype "bidirectional"))
    )
    (net (code "115") (name "unconnected-(X10-Pad46)") (class "Default")
      (node (ref "X10") (pin "46") (pinfunction "46_46") (pintype "bidirectional"))
    )
    (net (code "116") (name "unconnected-(X10-Pad47)") (class "Default")
      (node (ref "X10") (pin "47") (pinfunction "47_47") (pintype "bidirectional"))
    )
    (net (code "117") (name "unconnected-(X10-Pad49)") (class "Default")
      (node (ref "X10") (pin "49") (pinfunction "49_49") (pintype "bidirectional"))
    )
    (net (code "118") (name "unconnected-(X10-Pad50)") (class "Default")
      (node (ref "X10") (pin "50") (pinfunction "50_50") (pintype "bidirectional"))
    )
    (net (code "119") (name "unconnected-(X10-Pad51)") (class "Default")
      (node (ref "X10") (pin "51") (pinfunction "51_51") (pintype "bidirectional"))
    )
    (net (code "120") (name "unconnected-(X10-Pad52)") (class "Default")
      (node (ref "X10") (pin "52") (pinfunction "52_52") (pintype "bidirectional"))
    )
    (net (code "121") (name "unconnected-(X10-Pad53)") (class "Default")
      (node (ref "X10") (pin "53") (pinfunction "53_53") (pintype "bidirectional"))
    )
    (net (code "122") (name "unconnected-(X10-Pad54)") (class "Default")
      (node (ref "X10") (pin "54") (pinfunction "54_54") (pintype "bidirectional"))
    )
    (net (code "123") (name "unconnected-(X10-Pad55)") (class "Default")
      (node (ref "X10") (pin "55") (pinfunction "55_55") (pintype "bidirectional"))
    )
    (net (code "124") (name "unconnected-(X10-Pad59)") (class "Default")
      (node (ref "X10") (pin "59") (pinfunction "59_59") (pintype "bidirectional"))
    )
    (net (code "125") (name "unconnected-(X10-Pad61)") (class "Default")
      (node (ref "X10") (pin "61") (pinfunction "61_61") (pintype "bidirectional"))
    )
    (net (code "126") (name "unconnected-(X10-Pad63)") (class "Default")
      (node (ref "X10") (pin "63") (pinfunction "63_63") (pintype "bidirectional"))
    )
    (net (code "127") (name "unconnected-(X10-Pad65)") (class "Default")
      (node (ref "X10") (pin "65") (pinfunction "65_65") (pintype "bidirectional"))
    )
    (net (code "128") (name "unconnected-(X10-Pad68)") (class "Default")
      (node (ref "X10") (pin "68") (pinfunction "68_68") (pintype "bidirectional"))
    )
    (net (code "129") (name "unconnected-(X10-Pad69)") (class "Default")
      (node (ref "X10") (pin "69") (pinfunction "69_69") (pintype "bidirectional"))
    )
    (net (code "130") (name "unconnected-(X10-Pad70)") (class "Default")
      (node (ref "X10") (pin "70") (pinfunction "70_70") (pintype "bidirectional"))
    )
    (net (code "131") (name "unconnected-(X10-Pad71)") (class "Default")
      (node (ref "X10") (pin "71") (pinfunction "71_71") (pintype "bidirectional"))
    )
    (net (code "132") (name "unconnected-(X10-Pad72)") (class "Default")
      (node (ref "X10") (pin "72") (pinfunction "72_72") (pintype "bidirectional"))
    )
    (net (code "133") (name "unconnected-(X10-Pad73)") (class "Default")
      (node (ref "X10") (pin "73") (pinfunction "73_73") (pintype "bidirectional"))
    )
    (net (code "134") (name "unconnected-(X10-Pad74)") (class "Default")
      (node (ref "X10") (pin "74") (pinfunction "74_74") (pintype "bidirectional"))
    )
    (net (code "135") (name "unconnected-(X10-Pad75)") (class "Default")
      (node (ref "X10") (pin "75") (pinfunction "75_75") (pintype "bidirectional"))
    )
    (net (code "136") (name "unconnected-(X10-PadA8)") (class "Default")
      (node (ref "X10") (pin "A8") (pinfunction "A8_A8") (pintype "bidirectional"))
    )
    (net (code "137") (name "unconnected-(X10-PadA9)") (class "Default")
      (node (ref "X10") (pin "A9") (pinfunction "A9_A9") (pintype "bidirectional"))
    )
    (net (code "138") (name "unconnected-(X10-PadA10)") (class "Default")
      (node (ref "X10") (pin "A10") (pinfunction "A10_A10") (pintype "bidirectional"))
    )
    (net (code "139") (name "unconnected-(X10-PadA11)") (class "Default")
      (node (ref "X10") (pin "A11") (pinfunction "A11_A11") (pintype "bidirectional"))
    )
    (net (code "140") (name "unconnected-(X10-PadAREF)") (class "Default")
      (node (ref "X10") (pin "AREF") (pinfunction "AREF_AREF") (pintype "bidirectional"))
    )
    (net (code "141") (name "unconnected-(X10-PadCKN)") (class "Default")
      (node (ref "X10") (pin "CKN") (pinfunction "CKN_CKN") (pintype "bidirectional"))
    )
    (net (code "142") (name "unconnected-(X10-PadCKP)") (class "Default")
      (node (ref "X10") (pin "CKP") (pinfunction "CKP_CKP") (pintype "bidirectional"))
    )
    (net (code "143") (name "unconnected-(X10-PadD0N)") (class "Default")
      (node (ref "X10") (pin "D0N") (pinfunction "D0N_D0N") (pintype "bidirectional"))
    )
    (net (code "144") (name "unconnected-(X10-PadD0P)") (class "Default")
      (node (ref "X10") (pin "D0P") (pinfunction "D0P_D0P") (pintype "bidirectional"))
    )
    (net (code "145") (name "unconnected-(X10-PadD1N)") (class "Default")
      (node (ref "X10") (pin "D1N") (pinfunction "D1N_D1N") (pintype "bidirectional"))
    )
    (net (code "146") (name "unconnected-(X10-PadD1P)") (class "Default")
      (node (ref "X10") (pin "D1P") (pinfunction "D1P_D1P") (pintype "bidirectional"))
    )
    (net (code "147") (name "unconnected-(X10-PadIOREF)") (class "Default")
      (node (ref "X10") (pin "IOREF") (pinfunction "IOREF_IOREF") (pintype "bidirectional"))
    )
    (net (code "148") (name "unconnected-(X10-SCL-Pad21)") (class "Default")
      (node (ref "X10") (pin "21") (pinfunction "SCL_21") (pintype "bidirectional"))
    )
    (net (code "149") (name "unconnected-(X10-SDA-Pad20)") (class "Default")
      (node (ref "X10") (pin "20") (pinfunction "SDA_20") (pintype "bidirectional"))
    )
  )
)
